# hv3layerF.net
KiCad netlist of a schematic drawn in EAGLE
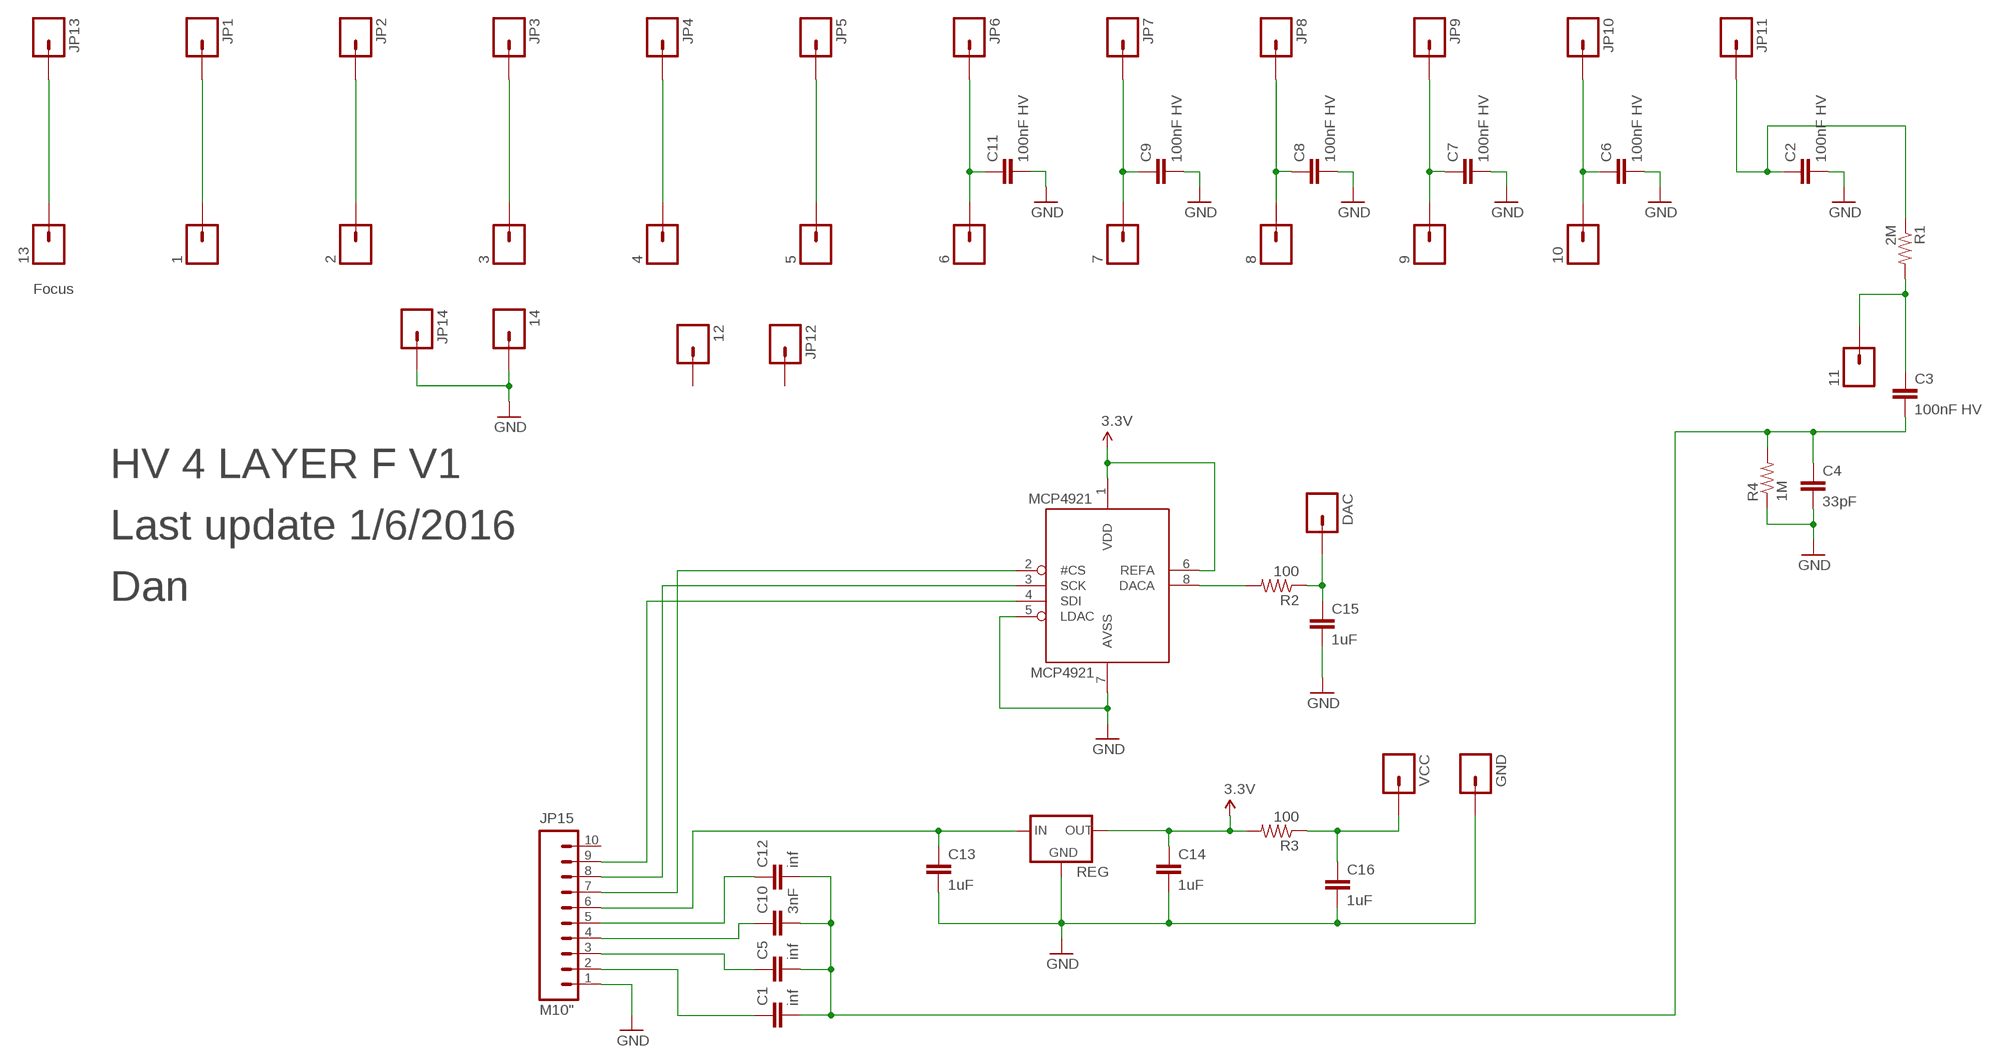
[diagram p0: schematic, sheet 1]

(export (version "E")
  (design (tool "Eeschema 10.0.6"))
  (components
    (comp (ref "1")
      (value "M01PTH")
      (footprint "eagle-import:1X01")
      (libsource (lib "eagle-import") (part "M01PTH"))
    )
    (comp (ref "2")
      (value "M01PTH")
      (footprint "eagle-import:1X01")
      (libsource (lib "eagle-import") (part "M01PTH"))
    )
    (comp (ref "3")
      (value "M01PTH")
      (footprint "eagle-import:1X01")
      (libsource (lib "eagle-import") (part "M01PTH"))
    )
    (comp (ref "4")
      (value "M01PTH")
      (footprint "eagle-import:1X01")
      (libsource (lib "eagle-import") (part "M01PTH"))
    )
    (comp (ref "5")
      (value "M01PTH")
      (footprint "eagle-import:1X01")
      (libsource (lib "eagle-import") (part "M01PTH"))
    )
    (comp (ref "6")
      (value "M01PTH")
      (footprint "eagle-import:1X01")
      (libsource (lib "eagle-import") (part "M01PTH"))
    )
    (comp (ref "7")
      (value "M01PTH")
      (footprint "eagle-import:1X01")
      (libsource (lib "eagle-import") (part "M01PTH"))
    )
    (comp (ref "8")
      (value "M01PTH")
      (footprint "eagle-import:1X01")
      (libsource (lib "eagle-import") (part "M01PTH"))
    )
    (comp (ref "9")
      (value "M01PTH")
      (footprint "eagle-import:1X01")
      (libsource (lib "eagle-import") (part "M01PTH"))
    )
    (comp (ref "10")
      (value "M01PTH")
      (footprint "eagle-import:1X01")
      (libsource (lib "eagle-import") (part "M01PTH"))
    )
    (comp (ref "11")
      (value "M01PTH")
      (footprint "eagle-import:1X01")
      (libsource (lib "eagle-import") (part "M01PTH"))
    )
    (comp (ref "12")
      (value "M01PTH")
      (footprint "eagle-import:1X01")
      (libsource (lib "eagle-import") (part "M01PTH"))
    )
    (comp (ref "13")
      (value "M01PTH")
      (footprint "eagle-import:1X01")
      (libsource (lib "eagle-import") (part "M01PTH"))
    )
    (comp (ref "14")
      (value "M01PTH")
      (footprint "eagle-import:1X01")
      (libsource (lib "eagle-import") (part "M01PTH"))
    )
    (comp (ref "C1")
      (value "inf")
      (footprint "eagle-import:0805")
      (libsource (lib "eagle-import") (part "CAP0805"))
    )
    (comp (ref "C2")
      (value "100nF HV")
      (footprint "eagle-import:C2225K")
      (libsource (lib "eagle-import") (part "C-EUC2225K"))
    )
    (comp (ref "C3")
      (value "100nF HV")
      (footprint "eagle-import:C2225K")
      (libsource (lib "eagle-import") (part "C-EUC2225K"))
    )
    (comp (ref "C4")
      (value "33pF")
      (footprint "eagle-import:0805")
      (libsource (lib "eagle-import") (part "CAP0805"))
    )
    (comp (ref "C5")
      (value "inf")
      (footprint "eagle-import:0805")
      (libsource (lib "eagle-import") (part "CAP0805"))
    )
    (comp (ref "C6")
      (value "100nF HV")
      (footprint "eagle-import:C2225K")
      (libsource (lib "eagle-import") (part "C-EUC2225K"))
    )
    (comp (ref "C7")
      (value "100nF HV")
      (footprint "eagle-import:C2225K")
      (libsource (lib "eagle-import") (part "C-EUC2225K"))
    )
    (comp (ref "C8")
      (value "100nF HV")
      (footprint "eagle-import:C2225K")
      (libsource (lib "eagle-import") (part "C-EUC2225K"))
    )
    (comp (ref "C9")
      (value "100nF HV")
      (footprint "eagle-import:C2225K")
      (libsource (lib "eagle-import") (part "C-EUC2225K"))
    )
    (comp (ref "C10")
      (value "3nF")
      (footprint "eagle-import:0805")
      (libsource (lib "eagle-import") (part "CAP0805"))
    )
    (comp (ref "C11")
      (value "100nF HV")
      (footprint "eagle-import:C2225K")
      (libsource (lib "eagle-import") (part "C-EUC2225K"))
    )
    (comp (ref "C12")
      (value "inf")
      (footprint "eagle-import:0805")
      (libsource (lib "eagle-import") (part "CAP0805"))
    )
    (comp (ref "C13")
      (value "1uF")
      (footprint "eagle-import:0805")
      (libsource (lib "eagle-import") (part "CAP0805"))
    )
    (comp (ref "C14")
      (value "1uF")
      (footprint "eagle-import:0805")
      (libsource (lib "eagle-import") (part "CAP0805"))
    )
    (comp (ref "C15")
      (value "1uF")
      (footprint "eagle-import:0805")
      (libsource (lib "eagle-import") (part "CAP0805"))
    )
    (comp (ref "C16")
      (value "1uF")
      (footprint "eagle-import:0805")
      (libsource (lib "eagle-import") (part "CAP0805"))
    )
    (comp (ref "DAC")
      (value "M01PTH")
      (footprint "eagle-import:1X01")
      (libsource (lib "eagle-import") (part "M01PTH"))
    )
    (comp (ref "GND")
      (value "M01PTH")
      (footprint "eagle-import:1X01")
      (libsource (lib "eagle-import") (part "M01PTH"))
    )
    (comp (ref "JP1")
      (value "M01PTH")
      (footprint "eagle-import:1X01")
      (libsource (lib "eagle-import") (part "M01PTH"))
    )
    (comp (ref "JP2")
      (value "M01PTH")
      (footprint "eagle-import:1X01")
      (libsource (lib "eagle-import") (part "M01PTH"))
    )
    (comp (ref "JP3")
      (value "M01PTH")
      (footprint "eagle-import:1X01")
      (libsource (lib "eagle-import") (part "M01PTH"))
    )
    (comp (ref "JP4")
      (value "M01PTH")
      (footprint "eagle-import:1X01")
      (libsource (lib "eagle-import") (part "M01PTH"))
    )
    (comp (ref "JP5")
      (value "M01PTH")
      (footprint "eagle-import:1X01")
      (libsource (lib "eagle-import") (part "M01PTH"))
    )
    (comp (ref "JP6")
      (value "M01PTH")
      (footprint "eagle-import:1X01")
      (libsource (lib "eagle-import") (part "M01PTH"))
    )
    (comp (ref "JP7")
      (value "M01PTH")
      (footprint "eagle-import:1X01")
      (libsource (lib "eagle-import") (part "M01PTH"))
    )
    (comp (ref "JP8")
      (value "M01PTH")
      (footprint "eagle-import:1X01")
      (libsource (lib "eagle-import") (part "M01PTH"))
    )
    (comp (ref "JP9")
      (value "M01PTH")
      (footprint "eagle-import:1X01")
      (libsource (lib "eagle-import") (part "M01PTH"))
    )
    (comp (ref "JP10")
      (value "M01PTH")
      (footprint "eagle-import:1X01")
      (libsource (lib "eagle-import") (part "M01PTH"))
    )
    (comp (ref "JP11")
      (value "M01PTH")
      (footprint "eagle-import:1X01")
      (libsource (lib "eagle-import") (part "M01PTH"))
    )
    (comp (ref "JP12")
      (value "M01PTH")
      (footprint "eagle-import:1X01")
      (libsource (lib "eagle-import") (part "M01PTH"))
    )
    (comp (ref "JP13")
      (value "M01PTH")
      (footprint "eagle-import:1X01")
      (libsource (lib "eagle-import") (part "M01PTH"))
    )
    (comp (ref "JP14")
      (value "M01PTH")
      (footprint "eagle-import:1X01")
      (libsource (lib "eagle-import") (part "M01PTH"))
    )
    (comp (ref "JP15")
      (value "M10\"")
      (footprint "eagle-import:1X10")
      (libsource (lib "eagle-import") (part "M10{dblquote}"))
    )
    (comp (ref "MCP4921")
      (value "MCP4921D")
      (footprint "eagle-import:SO08")
      (libsource (lib "eagle-import") (part "MCP4921D"))
    )
    (comp (ref "R1")
      (value "2M")
      (footprint "eagle-import:0805")
      (libsource (lib "eagle-import") (part "RESISTOR0805-RES"))
    )
    (comp (ref "R2")
      (value "100")
      (footprint "eagle-import:0805")
      (libsource (lib "eagle-import") (part "RESISTOR0805-RES"))
    )
    (comp (ref "R3")
      (value "100")
      (footprint "eagle-import:0805")
      (libsource (lib "eagle-import") (part "RESISTOR0805-RES"))
    )
    (comp (ref "R4")
      (value "1M")
      (footprint "eagle-import:0805")
      (libsource (lib "eagle-import") (part "RESISTOR0805-RES"))
    )
    (comp (ref "REG")
      (value "XC63FPM")
      (footprint "eagle-import:SOT23")
      (libsource (lib "eagle-import") (part "XC63FPM"))
    )
    (comp (ref "VCC")
      (value "M01PTH")
      (footprint "eagle-import:1X01")
      (libsource (lib "eagle-import") (part "M01PTH"))
    )
  )
  (nets
    (net (code "1") (name "3.3V") (class "Default")
      (node (ref "C14") (pin "1") (pinfunction "1_1") (pintype "passive"))
      (node (ref "MCP4921") (pin "1") (pinfunction "VDD_1") (pintype "power_in"))
      (node (ref "MCP4921") (pin "6") (pinfunction "REFA_6") (pintype "input"))
      (node (ref "R3") (pin "2") (pinfunction "2_2") (pintype "passive"))
      (node (ref "REG") (pin "2") (pinfunction "OUT_2") (pintype "passive"))
    )
    (net (code "2") (name "GND") (class "Default")
      (node (ref "14") (pin "1") (pinfunction "1_1") (pintype "passive"))
      (node (ref "C11") (pin "2") (pinfunction "2_2") (pintype "passive"))
      (node (ref "C13") (pin "2") (pinfunction "2_2") (pintype "passive"))
      (node (ref "C14") (pin "2") (pinfunction "2_2") (pintype "passive"))
      (node (ref "C15") (pin "2") (pinfunction "2_2") (pintype "passive"))
      (node (ref "C16") (pin "2") (pinfunction "2_2") (pintype "passive"))
      (node (ref "C2") (pin "2") (pinfunction "2_2") (pintype "passive"))
      (node (ref "C4") (pin "2") (pinfunction "2_2") (pintype "passive"))
      (node (ref "C6") (pin "2") (pinfunction "2_2") (pintype "passive"))
      (node (ref "C7") (pin "2") (pinfunction "2_2") (pintype "passive"))
      (node (ref "C8") (pin "2") (pinfunction "2_2") (pintype "passive"))
      (node (ref "C9") (pin "2") (pinfunction "2_2") (pintype "passive"))
      (node (ref "GND") (pin "1") (pinfunction "1_1") (pintype "passive"))
      (node (ref "JP14") (pin "1") (pinfunction "1_1") (pintype "passive"))
      (node (ref "JP15") (pin "1") (pinfunction "1_1") (pintype "passive"))
      (node (ref "MCP4921") (pin "5") (pinfunction "LDAC_5") (pintype "input"))
      (node (ref "MCP4921") (pin "7") (pinfunction "AVSS_7") (pintype "power_in"))
      (node (ref "R4") (pin "1") (pinfunction "1_1") (pintype "passive"))
      (node (ref "REG") (pin "1") (pinfunction "GND_1") (pintype "input"))
    )
    (net (code "3") (name "Net-(1-Pad1)") (class "Default")
      (node (ref "1") (pin "1") (pinfunction "1_1") (pintype "passive"))
      (node (ref "JP1") (pin "1") (pinfunction "1_1") (pintype "passive"))
    )
    (net (code "4") (name "Net-(2-Pad1)") (class "Default")
      (node (ref "2") (pin "1") (pinfunction "1_1") (pintype "passive"))
      (node (ref "JP2") (pin "1") (pinfunction "1_1") (pintype "passive"))
    )
    (net (code "5") (name "Net-(3-Pad1)") (class "Default")
      (node (ref "3") (pin "1") (pinfunction "1_1") (pintype "passive"))
      (node (ref "JP3") (pin "1") (pinfunction "1_1") (pintype "passive"))
    )
    (net (code "6") (name "Net-(4-Pad1)") (class "Default")
      (node (ref "4") (pin "1") (pinfunction "1_1") (pintype "passive"))
      (node (ref "JP4") (pin "1") (pinfunction "1_1") (pintype "passive"))
    )
    (net (code "7") (name "Net-(5-Pad1)") (class "Default")
      (node (ref "5") (pin "1") (pinfunction "1_1") (pintype "passive"))
      (node (ref "JP5") (pin "1") (pinfunction "1_1") (pintype "passive"))
    )
    (net (code "8") (name "Net-(6-Pad1)") (class "Default")
      (node (ref "6") (pin "1") (pinfunction "1_1") (pintype "passive"))
      (node (ref "C11") (pin "1") (pinfunction "1_1") (pintype "passive"))
      (node (ref "JP6") (pin "1") (pinfunction "1_1") (pintype "passive"))
    )
    (net (code "9") (name "Net-(7-Pad1)") (class "Default")
      (node (ref "7") (pin "1") (pinfunction "1_1") (pintype "passive"))
      (node (ref "C9") (pin "1") (pinfunction "1_1") (pintype "passive"))
      (node (ref "JP7") (pin "1") (pinfunction "1_1") (pintype "passive"))
    )
    (net (code "10") (name "Net-(8-Pad1)") (class "Default")
      (node (ref "8") (pin "1") (pinfunction "1_1") (pintype "passive"))
      (node (ref "C8") (pin "1") (pinfunction "1_1") (pintype "passive"))
      (node (ref "JP8") (pin "1") (pinfunction "1_1") (pintype "passive"))
    )
    (net (code "11") (name "Net-(9-Pad1)") (class "Default")
      (node (ref "9") (pin "1") (pinfunction "1_1") (pintype "passive"))
      (node (ref "C7") (pin "1") (pinfunction "1_1") (pintype "passive"))
      (node (ref "JP9") (pin "1") (pinfunction "1_1") (pintype "passive"))
    )
    (net (code "12") (name "Net-(10-Pad1)") (class "Default")
      (node (ref "10") (pin "1") (pinfunction "1_1") (pintype "passive"))
      (node (ref "C6") (pin "1") (pinfunction "1_1") (pintype "passive"))
      (node (ref "JP10") (pin "1") (pinfunction "1_1") (pintype "passive"))
    )
    (net (code "13") (name "Net-(11-Pad1)") (class "Default")
      (node (ref "11") (pin "1") (pinfunction "1_1") (pintype "passive"))
      (node (ref "C3") (pin "1") (pinfunction "1_1") (pintype "passive"))
      (node (ref "R1") (pin "2") (pinfunction "2_2") (pintype "passive"))
    )
    (net (code "14") (name "Net-(13-Pad1)") (class "Default")
      (node (ref "13") (pin "1") (pinfunction "1_1") (pintype "passive"))
      (node (ref "JP13") (pin "1") (pinfunction "1_1") (pintype "passive"))
    )
    (net (code "15") (name "Net-(C1-Pad1)") (class "Default")
      (node (ref "C1") (pin "1") (pinfunction "1_1") (pintype "passive"))
      (node (ref "JP15") (pin "2") (pinfunction "2_2") (pintype "passive"))
    )
    (net (code "16") (name "Net-(C1-Pad2)") (class "Default")
      (node (ref "C1") (pin "2") (pinfunction "2_2") (pintype "passive"))
      (node (ref "C10") (pin "2") (pinfunction "2_2") (pintype "passive"))
      (node (ref "C12") (pin "2") (pinfunction "2_2") (pintype "passive"))
      (node (ref "C3") (pin "2") (pinfunction "2_2") (pintype "passive"))
      (node (ref "C4") (pin "1") (pinfunction "1_1") (pintype "passive"))
      (node (ref "C5") (pin "2") (pinfunction "2_2") (pintype "passive"))
      (node (ref "R4") (pin "2") (pinfunction "2_2") (pintype "passive"))
    )
    (net (code "17") (name "Net-(C2-Pad1)") (class "Default")
      (node (ref "C2") (pin "1") (pinfunction "1_1") (pintype "passive"))
      (node (ref "JP11") (pin "1") (pinfunction "1_1") (pintype "passive"))
      (node (ref "R1") (pin "1") (pinfunction "1_1") (pintype "passive"))
    )
    (net (code "18") (name "Net-(C5-Pad1)") (class "Default")
      (node (ref "C5") (pin "1") (pinfunction "1_1") (pintype "passive"))
      (node (ref "JP15") (pin "3") (pinfunction "3_3") (pintype "passive"))
    )
    (net (code "19") (name "Net-(C10-Pad1)") (class "Default")
      (node (ref "C10") (pin "1") (pinfunction "1_1") (pintype "passive"))
      (node (ref "JP15") (pin "4") (pinfunction "4_4") (pintype "passive"))
    )
    (net (code "20") (name "Net-(C12-Pad1)") (class "Default")
      (node (ref "C12") (pin "1") (pinfunction "1_1") (pintype "passive"))
      (node (ref "JP15") (pin "5") (pinfunction "5_5") (pintype "passive"))
    )
    (net (code "21") (name "Net-(C15-Pad1)") (class "Default")
      (node (ref "C15") (pin "1") (pinfunction "1_1") (pintype "passive"))
      (node (ref "DAC") (pin "1") (pinfunction "1_1") (pintype "passive"))
      (node (ref "R2") (pin "1") (pinfunction "1_1") (pintype "passive"))
    )
    (net (code "22") (name "Net-(C16-Pad1)") (class "Default")
      (node (ref "C16") (pin "1") (pinfunction "1_1") (pintype "passive"))
      (node (ref "R3") (pin "1") (pinfunction "1_1") (pintype "passive"))
      (node (ref "VCC") (pin "1") (pinfunction "1_1") (pintype "passive"))
    )
    (net (code "23") (name "Net-(MCP4921-#CS)") (class "Default")
      (node (ref "JP15") (pin "7") (pinfunction "7_7") (pintype "passive"))
      (node (ref "MCP4921") (pin "2") (pinfunction "#CS_2") (pintype "input"))
    )
    (net (code "24") (name "Net-(MCP4921-DACA)") (class "Default")
      (node (ref "MCP4921") (pin "8") (pinfunction "DACA_8") (pintype "output"))
      (node (ref "R2") (pin "2") (pinfunction "2_2") (pintype "passive"))
    )
    (net (code "25") (name "Net-(MCP4921-SCK)") (class "Default")
      (node (ref "JP15") (pin "8") (pinfunction "8_8") (pintype "passive"))
      (node (ref "MCP4921") (pin "3") (pinfunction "SCK_3") (pintype "input"))
    )
    (net (code "26") (name "Net-(MCP4921-SDI)") (class "Default")
      (node (ref "JP15") (pin "9") (pinfunction "9_9") (pintype "passive"))
      (node (ref "MCP4921") (pin "4") (pinfunction "SDI_4") (pintype "input"))
    )
    (net (code "27") (name "Net-(REG-IN)") (class "Default")
      (node (ref "C13") (pin "1") (pinfunction "1_1") (pintype "passive"))
      (node (ref "JP15") (pin "6") (pinfunction "6_6") (pintype "passive"))
      (node (ref "REG") (pin "3") (pinfunction "IN_3") (pintype "input"))
    )
    (net (code "28") (name "unconnected-(12-Pad1)") (class "Default")
      (node (ref "12") (pin "1") (pinfunction "1_1") (pintype "passive"))
    )
    (net (code "29") (name "unconnected-(JP12-Pad1)") (class "Default")
      (node (ref "JP12") (pin "1") (pinfunction "1_1") (pintype "passive"))
    )
    (net (code "30") (name "unconnected-(JP15-Pad10)") (class "Default")
      (node (ref "JP15") (pin "10") (pinfunction "10_10") (pintype "passive"))
    )
  )
)
